# roundboard_-_MDBT42Q_ICM20848_new.net
KiCad netlist of a schematic drawn in EAGLE
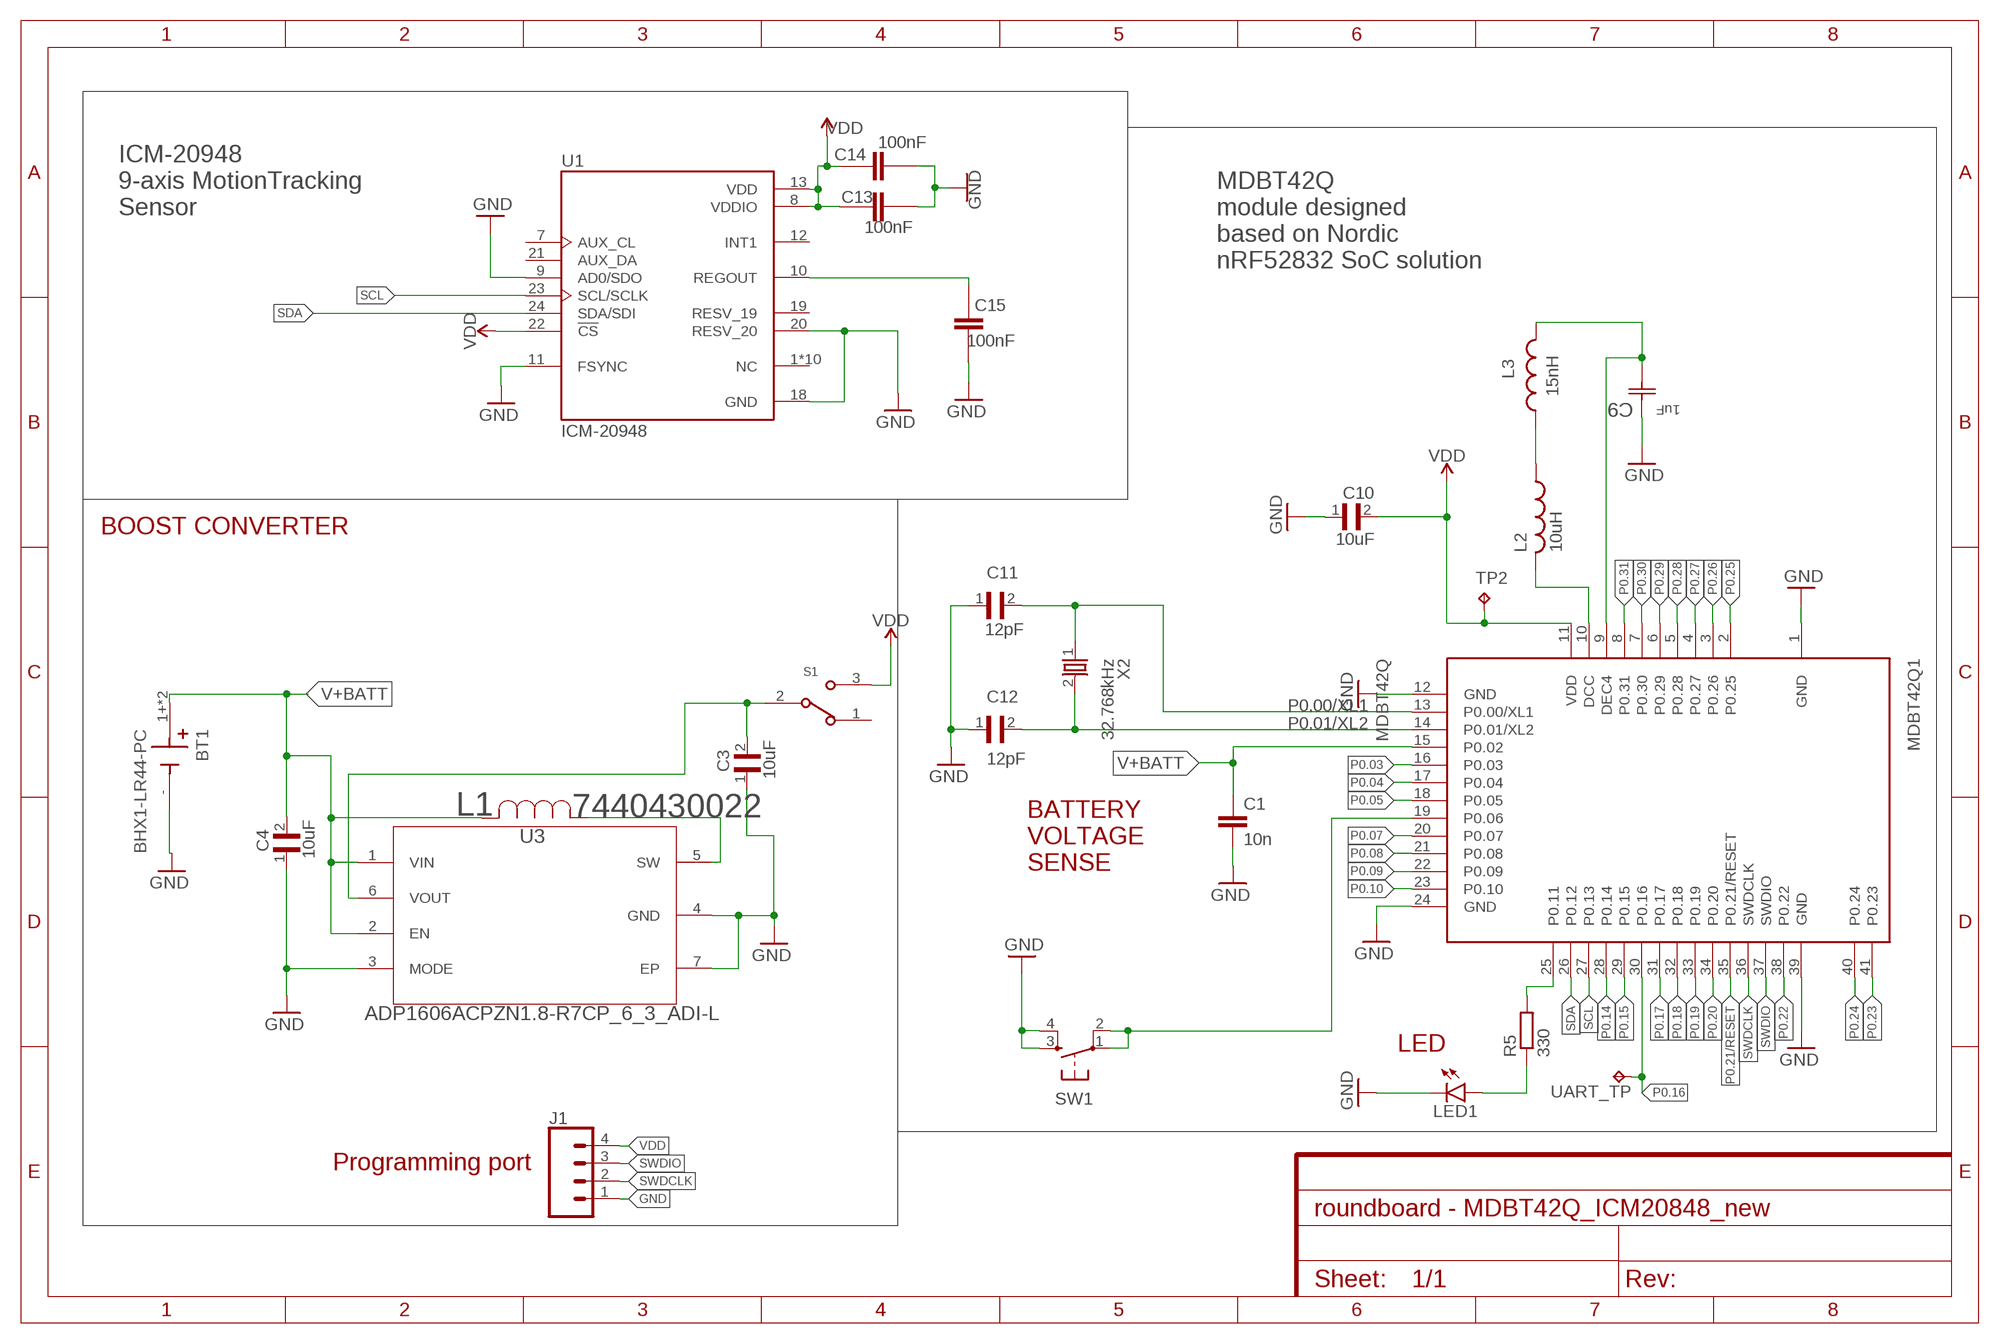
[diagram p0: schematic, sheet 1]

(export (version "E")
  (design (tool "Eeschema 10.0.6"))
  (components
    (comp (ref "BT1")
      (value "BHX1-LR44-PC")
      (footprint "eagle-import:BAT_BHX1-LR44-PC")
      (fields (field (name "DIGI-KEY_PART_NUMBER") "BHX1-LR44-PC-G-ND") (field (name "MF") "MPD"))
      (libsource (lib "eagle-import") (part "BHX1-LR44-PC"))
    )
    (comp (ref "C1")
      (value "10n")
      (footprint "eagle-import:C0603")
      (libsource (lib "eagle-import") (part "C-EUC0603"))
    )
    (comp (ref "C3")
      (value "10uF")
      (footprint "eagle-import:CAPC1608X95N")
      (fields
        (field (name "DIGI-KEY_PART_NUMBER") "490-14372-1-ND")
        (field (name "MF") "Murata")
        (field (name "MP") "GRM188R61A106KE69J")
      )
      (libsource (lib "eagle-import") (part "GRM188R61A106KE69J"))
    )
    (comp (ref "C4")
      (value "10uF")
      (footprint "eagle-import:CAPC1608X95N")
      (fields
        (field (name "DIGI-KEY_PART_NUMBER") "490-14372-1-ND")
        (field (name "MF") "Murata")
        (field (name "MP") "GRM188R61A106KE69J")
      )
      (libsource (lib "eagle-import") (part "GRM188R61A106KE69J"))
    )
    (comp (ref "C9")
      (value "1uF")
      (footprint "eagle-import:CAPC1608X90N")
      (fields
        (field (name "DIGI-KEY_PART_NUMBER") "311-1446-1-ND")
        (field (name "MF") "Yageo")
        (field (name "MP") "CC0603KRX7R7BB105")
      )
      (libsource (lib "eagle-import") (part "CC0603KRX7R7BB105"))
    )
    (comp (ref "C10")
      (value "10uF")
      (footprint "eagle-import:CAPC1608X95N")
      (fields
        (field (name "DIGI-KEY_PART_NUMBER") "490-14372-1-ND")
        (field (name "MF") "Murata")
        (field (name "MP") "GRM188R61A106KE69J")
      )
      (libsource (lib "eagle-import") (part "GRM188R61A106KE69J"))
    )
    (comp (ref "C11")
      (value "12pF")
      (footprint "eagle-import:CAPC1005X56N")
      (fields
        (field (name "DIGI-KEY_PART_NUMBER") "478-7871-1-ND")
        (field (name "MF") "AVX")
        (field (name "MP") "04025A120GAT2A")
      )
      (libsource (lib "eagle-import") (part "04025A120GAT2A"))
    )
    (comp (ref "C12")
      (value "12pF")
      (footprint "eagle-import:CAPC1005X56N")
      (fields
        (field (name "DIGI-KEY_PART_NUMBER") "478-7871-1-ND")
        (field (name "MF") "AVX")
        (field (name "MP") "04025A120GAT2A")
      )
      (libsource (lib "eagle-import") (part "04025A120GAT2A"))
    )
    (comp (ref "C13")
      (value "100nF")
      (footprint "eagle-import:CAPC1005X60")
      (fields
        (field (name "DIGI-KEY_PART_NUMBER") "311-1345-1-ND")
        (field (name "MF") "Yageo")
        (field (name "MP") "CC0402KRX7R6BB104")
      )
      (libsource (lib "eagle-import") (part "CC0402KRX7R6BB104"))
    )
    (comp (ref "C14")
      (value "100nF")
      (footprint "eagle-import:CAPC1005X60")
      (fields
        (field (name "DIGI-KEY_PART_NUMBER") "311-1345-1-ND")
        (field (name "MF") "Yageo")
        (field (name "MP") "CC0402KRX7R6BB104")
      )
      (libsource (lib "eagle-import") (part "CC0402KRX7R6BB104"))
    )
    (comp (ref "C15")
      (value "100nF")
      (footprint "eagle-import:CAPC1005X60")
      (fields
        (field (name "DIGI-KEY_PART_NUMBER") "311-1345-1-ND")
        (field (name "MF") "Yageo")
        (field (name "MP") "CC0402KRX7R6BB104")
      )
      (libsource (lib "eagle-import") (part "CC0402KRX7R6BB104"))
    )
    (comp (ref "J1")
      (value "CONN_04PTH")
      (footprint "eagle-import:1X04")
      (libsource (lib "eagle-import") (part "CONN_04PTH"))
    )
    (comp (ref "L1")
      (value "7440430022")
      (footprint "eagle-import:IND_7440430022_WRE")
      (fields (field (name "COPYRIGHT") "Copyright (C) 2018 Accelerated Designs. All rights reserved"))
      (libsource (lib "eagle-import") (part "7440430022"))
    )
    (comp (ref "L2")
      (value "10uH")
      (footprint "eagle-import:RESC0603_L")
      (libsource (lib "eagle-import") (part "INDUCTOR_0603_L"))
    )
    (comp (ref "L3")
      (value "15nH")
      (footprint "eagle-import:INDC1005X55N")
      (fields
        (field (name "DIGI-KEY_PART_NUMBER") "490-2625-1-ND")
        (field (name "MF") "Murata Electronics")
        (field (name "MP") "LQG15HS15NJ02D")
      )
      (libsource (lib "eagle-import") (part "LQG15HS15NJ02D"))
    )
    (comp (ref "LED1")
      (value "LEDCHIPLED_1206")
      (footprint "eagle-import:CHIPLED_1206")
      (libsource (lib "eagle-import") (part "LEDCHIPLED_1206"))
    )
    (comp (ref "MDBT42Q1")
      (value "MDBT42Q")
      (footprint "eagle-import:MDBT42Q")
      (libsource (lib "eagle-import") (part "MDBT42Q"))
    )
    (comp (ref "R5")
      (value "330")
      (footprint "eagle-import:R0603")
      (libsource (lib "eagle-import") (part "R-EU_R0603"))
    )
    (comp (ref "S1")
      (value "JS102011SAQN")
      (footprint "eagle-import:SW_JS102011SAQN")
      (fields (field (name "DIGI-KEY_PART_NUMBER") "401-1999-1-ND") (field (name "MF") "C&K"))
      (libsource (lib "eagle-import") (part "JS102011SAQN"))
    )
    (comp (ref "SW1")
      (value "SWITCH_SPST_4_PINRECT")
      (footprint "eagle-import:TACTILE_SWITCH_SMD_4.6X2.8MM")
      (libsource (lib "eagle-import") (part "SWITCH_SPST_4_PINRECT"))
    )
    (comp (ref "TP2")
      (value "TPB1,27")
      (footprint "eagle-import:B1,27")
      (libsource (lib "eagle-import") (part "TPB1,27"))
    )
    (comp (ref "U1")
      (value "ICM-20948")
      (footprint "eagle-import:QFN40P300X300X105-24N")
      (fields (field (name "MF") "TDK InvenSense"))
      (libsource (lib "eagle-import") (part "ICM-20948"))
    )
    (comp (ref "U3")
      (value "ADP1606ACPZN1.8-R7CP_6_3_ADI-L")
      (footprint "eagle-import:CP_6_3_ADI-L")
      (fields (field (name "MANUFACTURER_PART_NUMBER") "ADP1606ACPZN1.8-R7"))
      (libsource (lib "eagle-import") (part "ADP1606ACPZN1.8-R7CP_6_3_ADI-L"))
    )
    (comp (ref "UART_TP")
      (value "TPB1,27")
      (footprint "eagle-import:B1,27")
      (libsource (lib "eagle-import") (part "TPB1,27"))
    )
    (comp (ref "X2")
      (value "32.768kHz")
      (footprint "eagle-import:XTAL_3215_N")
      (libsource (lib "eagle-import") (part "XTAL_32KHZ"))
    )
  )
  (nets
    (net (code "1") (name "/P0.00{slash}XL1") (class "Default")
      (node (ref "C11") (pin "2") (pinfunction "2_2") (pintype "passive"))
      (node (ref "MDBT42Q1") (pin "13") (pinfunction "P0.00/XL1_13") (pintype "bidirectional"))
      (node (ref "X2") (pin "1") (pinfunction "1_1") (pintype "passive"))
    )
    (net (code "2") (name "/P0.01{slash}XL2") (class "Default")
      (node (ref "C12") (pin "2") (pinfunction "2_2") (pintype "passive"))
      (node (ref "MDBT42Q1") (pin "14") (pinfunction "P0.01/XL2_14") (pintype "bidirectional"))
      (node (ref "X2") (pin "2") (pinfunction "2_2") (pintype "passive"))
    )
    (net (code "3") (name "GND") (class "Default")
      (node (ref "BT1") (pin "-") (pinfunction "-_-") (pintype "passive"))
      (node (ref "C1") (pin "2") (pinfunction "2_2") (pintype "passive"))
      (node (ref "C10") (pin "1") (pinfunction "1_1") (pintype "passive"))
      (node (ref "C11") (pin "1") (pinfunction "1_1") (pintype "passive"))
      (node (ref "C12") (pin "1") (pinfunction "1_1") (pintype "passive"))
      (node (ref "C13") (pin "1") (pinfunction "1_1") (pintype "passive"))
      (node (ref "C14") (pin "1") (pinfunction "1_1") (pintype "passive"))
      (node (ref "C15") (pin "1") (pinfunction "1_1") (pintype "passive"))
      (node (ref "C3") (pin "1") (pinfunction "1_1") (pintype "passive"))
      (node (ref "C4") (pin "1") (pinfunction "1_1") (pintype "passive"))
      (node (ref "C9") (pin "1") (pinfunction "C1_1") (pintype "passive"))
      (node (ref "J1") (pin "1") (pinfunction "1_1") (pintype "passive"))
      (node (ref "LED1") (pin "C") (pinfunction "C_C") (pintype "passive"))
      (node (ref "MDBT42Q1") (pin "1") (pinfunction "GND_1") (pintype "bidirectional"))
      (node (ref "MDBT42Q1") (pin "12") (pinfunction "GND_12") (pintype "bidirectional"))
      (node (ref "MDBT42Q1") (pin "24") (pinfunction "GND_24") (pintype "bidirectional"))
      (node (ref "MDBT42Q1") (pin "39") (pinfunction "GND_39") (pintype "bidirectional"))
      (node (ref "SW1") (pin "3") (pinfunction "3_3") (pintype "passive"))
      (node (ref "SW1") (pin "4") (pinfunction "4_4") (pintype "passive"))
      (node (ref "U1") (pin "11") (pinfunction "FSYNC_11") (pintype "input"))
      (node (ref "U1") (pin "18") (pinfunction "GND_18") (pintype "power_in"))
      (node (ref "U1") (pin "20") (pinfunction "RESV_20_20") (pintype "passive"))
      (node (ref "U1") (pin "9") (pinfunction "AD0/SDO_9") (pintype "bidirectional"))
      (node (ref "U3") (pin "3") (pinfunction "MODE_3") (pintype "passive"))
      (node (ref "U3") (pin "4") (pinfunction "GND_4") (pintype "passive"))
      (node (ref "U3") (pin "7") (pinfunction "EP_7") (pintype "passive"))
    )
    (net (code "4") (name "Net-(C9-C2)") (class "Default")
      (node (ref "C9") (pin "2") (pinfunction "C2_2") (pintype "passive"))
      (node (ref "L3") (pin "2") (pinfunction "2_2") (pintype "passive"))
      (node (ref "MDBT42Q1") (pin "9") (pinfunction "DEC4_9") (pintype "bidirectional"))
    )
    (net (code "5") (name "Net-(L2-Pad1)") (class "Default")
      (node (ref "L2") (pin "1") (pinfunction "1_1") (pintype "passive"))
      (node (ref "L3") (pin "1") (pinfunction "1_1") (pintype "passive"))
    )
    (net (code "6") (name "Net-(LED1-PadA)") (class "Default")
      (node (ref "LED1") (pin "A") (pinfunction "A_A") (pintype "passive"))
      (node (ref "R5") (pin "1") (pinfunction "1_1") (pintype "passive"))
    )
    (net (code "7") (name "Net-(MDBT42Q1-DCC)") (class "Default")
      (node (ref "L2") (pin "2") (pinfunction "2_2") (pintype "passive"))
      (node (ref "MDBT42Q1") (pin "10") (pinfunction "DCC_10") (pintype "bidirectional"))
    )
    (net (code "8") (name "Net-(MDBT42Q1-P0.06)") (class "Default")
      (node (ref "MDBT42Q1") (pin "19") (pinfunction "P0.06_19") (pintype "bidirectional"))
      (node (ref "SW1") (pin "1") (pinfunction "1_1") (pintype "passive"))
      (node (ref "SW1") (pin "2") (pinfunction "2_2") (pintype "passive"))
    )
    (net (code "9") (name "Net-(MDBT42Q1-P0.11)") (class "Default")
      (node (ref "MDBT42Q1") (pin "25") (pinfunction "P0.11_25") (pintype "bidirectional"))
      (node (ref "R5") (pin "2") (pinfunction "2_2") (pintype "passive"))
    )
    (net (code "10") (name "Net-(U1-REGOUT)") (class "Default")
      (node (ref "C15") (pin "2") (pinfunction "2_2") (pintype "passive"))
      (node (ref "U1") (pin "10") (pinfunction "REGOUT_10") (pintype "output"))
    )
    (net (code "11") (name "Net-(U3-SW)") (class "Default")
      (node (ref "L1") (pin "1") (pinfunction "1_1") (pintype "passive"))
      (node (ref "U3") (pin "5") (pinfunction "SW_5") (pintype "passive"))
    )
    (net (code "12") (name "Net-(U3-VOUT)") (class "Default")
      (node (ref "C3") (pin "2") (pinfunction "2_2") (pintype "passive"))
      (node (ref "S1") (pin "2") (pinfunction "2_2") (pintype "passive"))
      (node (ref "U3") (pin "6") (pinfunction "VOUT_6") (pintype "passive"))
    )
    (net (code "13") (name "P0.03") (class "Default")
      (node (ref "MDBT42Q1") (pin "16") (pinfunction "P0.03_16") (pintype "bidirectional"))
    )
    (net (code "14") (name "P0.04") (class "Default")
      (node (ref "MDBT42Q1") (pin "17") (pinfunction "P0.04_17") (pintype "bidirectional"))
    )
    (net (code "15") (name "P0.05") (class "Default")
      (node (ref "MDBT42Q1") (pin "18") (pinfunction "P0.05_18") (pintype "bidirectional"))
    )
    (net (code "16") (name "P0.07") (class "Default")
      (node (ref "MDBT42Q1") (pin "20") (pinfunction "P0.07_20") (pintype "bidirectional"))
    )
    (net (code "17") (name "P0.08") (class "Default")
      (node (ref "MDBT42Q1") (pin "21") (pinfunction "P0.08_21") (pintype "bidirectional"))
    )
    (net (code "18") (name "P0.09") (class "Default")
      (node (ref "MDBT42Q1") (pin "22") (pinfunction "P0.09_22") (pintype "bidirectional"))
    )
    (net (code "19") (name "P0.10") (class "Default")
      (node (ref "MDBT42Q1") (pin "23") (pinfunction "P0.10_23") (pintype "bidirectional"))
    )
    (net (code "20") (name "P0.14") (class "Default")
      (node (ref "MDBT42Q1") (pin "28") (pinfunction "P0.14_28") (pintype "bidirectional"))
    )
    (net (code "21") (name "P0.15") (class "Default")
      (node (ref "MDBT42Q1") (pin "29") (pinfunction "P0.15_29") (pintype "bidirectional"))
    )
    (net (code "22") (name "P0.16") (class "Default")
      (node (ref "MDBT42Q1") (pin "30") (pinfunction "P0.16_30") (pintype "bidirectional"))
      (node (ref "UART_TP") (pin "TP") (pinfunction "TP_TP") (pintype "input"))
    )
    (net (code "23") (name "P0.17") (class "Default")
      (node (ref "MDBT42Q1") (pin "31") (pinfunction "P0.17_31") (pintype "bidirectional"))
    )
    (net (code "24") (name "P0.18") (class "Default")
      (node (ref "MDBT42Q1") (pin "32") (pinfunction "P0.18_32") (pintype "bidirectional"))
    )
    (net (code "25") (name "P0.19") (class "Default")
      (node (ref "MDBT42Q1") (pin "33") (pinfunction "P0.19_33") (pintype "bidirectional"))
    )
    (net (code "26") (name "P0.20") (class "Default")
      (node (ref "MDBT42Q1") (pin "34") (pinfunction "P0.20_34") (pintype "bidirectional"))
    )
    (net (code "27") (name "P0.21{slash}RESET") (class "Default")
      (node (ref "MDBT42Q1") (pin "35") (pinfunction "P0.21/RESET_35") (pintype "bidirectional"))
    )
    (net (code "28") (name "P0.22") (class "Default")
      (node (ref "MDBT42Q1") (pin "38") (pinfunction "P0.22_38") (pintype "bidirectional"))
    )
    (net (code "29") (name "P0.23") (class "Default")
      (node (ref "MDBT42Q1") (pin "41") (pinfunction "P0.23_41") (pintype "bidirectional"))
    )
    (net (code "30") (name "P0.24") (class "Default")
      (node (ref "MDBT42Q1") (pin "40") (pinfunction "P0.24_40") (pintype "bidirectional"))
    )
    (net (code "31") (name "P0.25") (class "Default")
      (node (ref "MDBT42Q1") (pin "2") (pinfunction "P0.25_2") (pintype "bidirectional"))
    )
    (net (code "32") (name "P0.26") (class "Default")
      (node (ref "MDBT42Q1") (pin "3") (pinfunction "P0.26_3") (pintype "bidirectional"))
    )
    (net (code "33") (name "P0.27") (class "Default")
      (node (ref "MDBT42Q1") (pin "4") (pinfunction "P0.27_4") (pintype "bidirectional"))
    )
    (net (code "34") (name "P0.28") (class "Default")
      (node (ref "MDBT42Q1") (pin "5") (pinfunction "P0.28_5") (pintype "bidirectional"))
    )
    (net (code "35") (name "P0.29") (class "Default")
      (node (ref "MDBT42Q1") (pin "6") (pinfunction "P0.29_6") (pintype "bidirectional"))
    )
    (net (code "36") (name "P0.30") (class "Default")
      (node (ref "MDBT42Q1") (pin "7") (pinfunction "P0.30_7") (pintype "bidirectional"))
    )
    (net (code "37") (name "P0.31") (class "Default")
      (node (ref "MDBT42Q1") (pin "8") (pinfunction "P0.31_8") (pintype "bidirectional"))
    )
    (net (code "38") (name "SCL") (class "Default")
      (node (ref "MDBT42Q1") (pin "27") (pinfunction "P0.13_27") (pintype "bidirectional"))
      (node (ref "U1") (pin "23") (pinfunction "SCL/SCLK_23") (pintype "input"))
    )
    (net (code "39") (name "SDA") (class "Default")
      (node (ref "MDBT42Q1") (pin "26") (pinfunction "P0.12_26") (pintype "bidirectional"))
      (node (ref "U1") (pin "24") (pinfunction "SDA/SDI_24") (pintype "bidirectional"))
    )
    (net (code "40") (name "SWDCLK") (class "Default")
      (node (ref "J1") (pin "2") (pinfunction "2_2") (pintype "passive"))
      (node (ref "MDBT42Q1") (pin "36") (pinfunction "SWDCLK_36") (pintype "bidirectional"))
    )
    (net (code "41") (name "SWDIO") (class "Default")
      (node (ref "J1") (pin "3") (pinfunction "3_3") (pintype "passive"))
      (node (ref "MDBT42Q1") (pin "37") (pinfunction "SWDIO_37") (pintype "bidirectional"))
    )
    (net (code "42") (name "V+BATT") (class "Default")
      (node (ref "BT1") (pin "1+") (pinfunction "+_1+") (pintype "passive"))
      (node (ref "BT1") (pin "2+") (pinfunction "+_2+") (pintype "passive"))
      (node (ref "C1") (pin "1") (pinfunction "1_1") (pintype "passive"))
      (node (ref "C4") (pin "2") (pinfunction "2_2") (pintype "passive"))
      (node (ref "L1") (pin "2") (pinfunction "2_2") (pintype "passive"))
      (node (ref "MDBT42Q1") (pin "15") (pinfunction "P0.02_15") (pintype "bidirectional"))
      (node (ref "U3") (pin "1") (pinfunction "VIN_1") (pintype "passive"))
      (node (ref "U3") (pin "2") (pinfunction "EN_2") (pintype "passive"))
    )
    (net (code "43") (name "VDD") (class "Default")
      (node (ref "C10") (pin "2") (pinfunction "2_2") (pintype "passive"))
      (node (ref "C13") (pin "2") (pinfunction "2_2") (pintype "passive"))
      (node (ref "C14") (pin "2") (pinfunction "2_2") (pintype "passive"))
      (node (ref "J1") (pin "4") (pinfunction "4_4") (pintype "passive"))
      (node (ref "MDBT42Q1") (pin "11") (pinfunction "VDD_11") (pintype "bidirectional"))
      (node (ref "S1") (pin "3") (pinfunction "3_3") (pintype "passive"))
      (node (ref "TP2") (pin "TP") (pinfunction "TP_TP") (pintype "input"))
      (node (ref "U1") (pin "13") (pinfunction "VDD_13") (pintype "power_in"))
      (node (ref "U1") (pin "22") (pinfunction "~{CS}_22") (pintype "input"))
      (node (ref "U1") (pin "8") (pinfunction "VDDIO_8") (pintype "power_in"))
    )
    (net (code "44") (name "unconnected-(S1-Pad1)") (class "Default")
      (node (ref "S1") (pin "1") (pinfunction "1_1") (pintype "passive"))
    )
    (net (code "45") (name "unconnected-(U1-AUX_CL-Pad7)") (class "Default")
      (node (ref "U1") (pin "7") (pinfunction "AUX_CL_7") (pintype "input"))
    )
    (net (code "46") (name "unconnected-(U1-AUX_DA-Pad21)") (class "Default")
      (node (ref "U1") (pin "21") (pinfunction "AUX_DA_21") (pintype "bidirectional"))
    )
    (net (code "47") (name "unconnected-(U1-INT1-Pad12)") (class "Default")
      (node (ref "U1") (pin "12") (pinfunction "INT1_12") (pintype "output"))
    )
    (net (code "48") (name "unconnected-(U1-NC-Pad1)") (class "Default")
      (node (ref "U1") (pin "1") (pinfunction "NC_1") (pintype "no_connect"))
    )
    (net (code "49") (name "unconnected-(U1-NC-Pad2)") (class "Default")
      (node (ref "U1") (pin "2") (pinfunction "NC_2") (pintype "no_connect"))
    )
    (net (code "50") (name "unconnected-(U1-NC-Pad3)") (class "Default")
      (node (ref "U1") (pin "3") (pinfunction "NC_3") (pintype "no_connect"))
    )
    (net (code "51") (name "unconnected-(U1-NC-Pad4)") (class "Default")
      (node (ref "U1") (pin "4") (pinfunction "NC_4") (pintype "no_connect"))
    )
    (net (code "52") (name "unconnected-(U1-NC-Pad5)") (class "Default")
      (node (ref "U1") (pin "5") (pinfunction "NC_5") (pintype "no_connect"))
    )
    (net (code "53") (name "unconnected-(U1-NC-Pad6)") (class "Default")
      (node (ref "U1") (pin "6") (pinfunction "NC_6") (pintype "no_connect"))
    )
    (net (code "54") (name "unconnected-(U1-NC-Pad14)") (class "Default")
      (node (ref "U1") (pin "14") (pinfunction "NC_14") (pintype "no_connect"))
    )
    (net (code "55") (name "unconnected-(U1-NC-Pad15)") (class "Default")
      (node (ref "U1") (pin "15") (pinfunction "NC_15") (pintype "no_connect"))
    )
    (net (code "56") (name "unconnected-(U1-NC-Pad16)") (class "Default")
      (node (ref "U1") (pin "16") (pinfunction "NC_16") (pintype "no_connect"))
    )
    (net (code "57") (name "unconnected-(U1-NC-Pad17)") (class "Default")
      (node (ref "U1") (pin "17") (pinfunction "NC_17") (pintype "no_connect"))
    )
    (net (code "58") (name "unconnected-(U1-RESV_19-Pad19)") (class "Default")
      (node (ref "U1") (pin "19") (pinfunction "RESV_19_19") (pintype "passive"))
    )
  )
)
